# CAN.net
KiCad netlist of a schematic drawn in Altium Designer
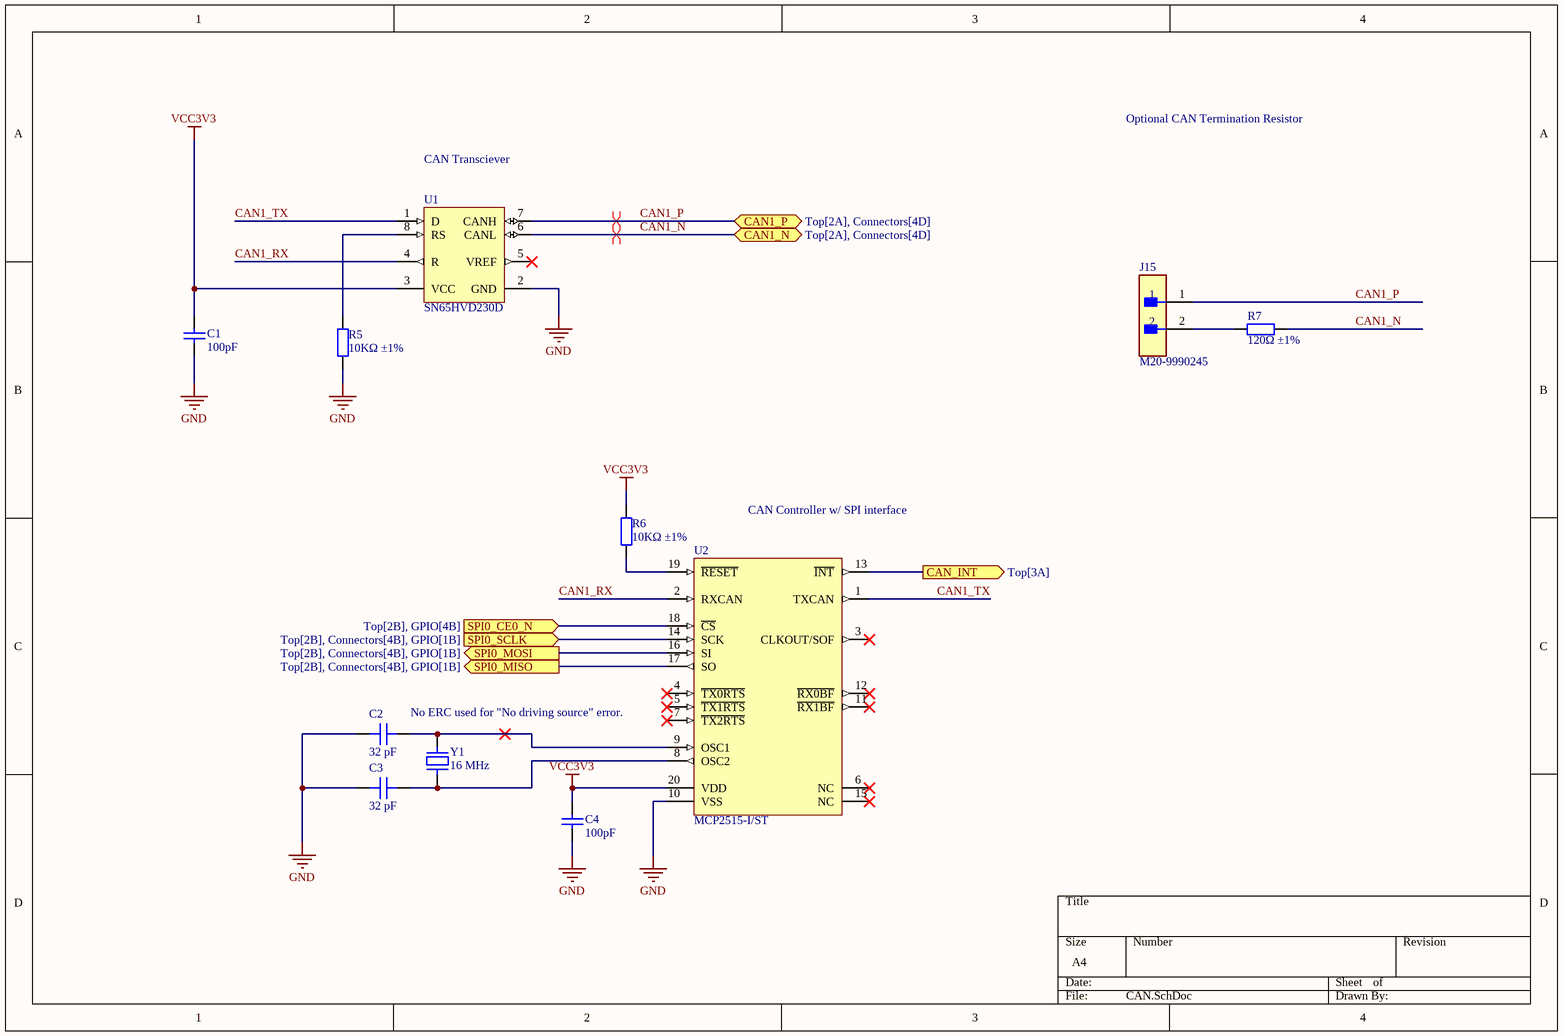
[diagram p0: CAN.SchDoc]

(export (version "E")
  (design (tool "Eeschema 10.0.6"))
  (components
    (comp (ref "C1")
      (value "100pF")
      (footprint "0402_C")
      (description "Chip capacitors")
      (fields
        (field (name "MANUFACTURER") "Guangdong Fenghua Advanced Tech")
        (field (name "PARTNUMBER") "0402CG101J500NT")
      )
      (libsource (lib "Cap") (part "0402 100pF (101) 5% 50V"))
    )
    (comp (ref "C2")
      (value "32 pF")
      (footprint "CAP 0603_1608")
      (description "CAP CER 32PF 100V C0G/NP0 0603")
      (fields (field (name "PART NUMBER") "06031A320FAT2A") (field (name "MANUFACTURER") "KYOCERA AVX"))
      (libsource (lib "Celestial Altium Library - altium_library") (part "Capacitor"))
    )
    (comp (ref "C3")
      (value "32 pF")
      (footprint "CAP 0603_1608")
      (description "CAP CER 32PF 100V C0G/NP0 0603")
      (fields (field (name "PART NUMBER") "06031A320FAT2A") (field (name "MANUFACTURER") "KYOCERA AVX"))
      (libsource (lib "Celestial Altium Library - altium_library") (part "Capacitor"))
    )
    (comp (ref "C4")
      (value "100pF")
      (footprint "0402_C")
      (description "Chip capacitors")
      (fields
        (field (name "MANUFACTURER") "Guangdong Fenghua Advanced Tech")
        (field (name "PARTNUMBER") "0402CG101J500NT")
      )
      (libsource (lib "Cap") (part "0402 100pF (101) 5% 50V"))
    )
    (comp (ref "J15")
      (value "M20-9990245")
      (footprint "FP-M20-9990245-MFG")
      (description "CONN HEADER VERT 2POS 2.54MM")
      (fields (field (name "VOLTAGE") "50V"))
      (libsource (lib "Altium Content Vault") (part "3bc925449376181038e59eaffc5286c"))
    )
    (comp (ref "R5")
      (value "10KΩ ±1%")
      (footprint "0402_R")
      (description "Chip resistor")
      (fields (field (name "MANUFACTURER") "Uniroyal Elec") (field (name "PARTNUMBER") "0402WGF1002TCE"))
      (libsource (lib "RES") (part "0402 10K (1002) 1%"))
    )
    (comp (ref "R6")
      (value "10KΩ ±1%")
      (footprint "0402_R")
      (description "Chip resistor")
      (fields (field (name "MANUFACTURER") "Uniroyal Elec") (field (name "PARTNUMBER") "0402WGF1002TCE"))
      (libsource (lib "RES") (part "0402 10K (1002) 1%"))
    )
    (comp (ref "R7")
      (value "120Ω ±1%")
      (footprint "0603_R")
      (description "Chip resistor")
      (fields (field (name "MANUFACTURER") "Uniroyal Elec") (field (name "PARTNUMBER") "0603WAF1200T5E"))
      (libsource (lib "RES") (part "0603 120R (1200) 1%"))
    )
    (comp (ref "U1")
      (value "SN65HVD230D")
      (footprint "D0008A_M")
      (description "CAN Bus Transceiver, 3.3 V, -40 to 85 degC, 8-Pin SOIC (D), Green (RoHS & no Sb/Br), Tube")
      (fields (field (name "GENERIC PART NUMBER") "SN65HVD230"))
      (libsource (lib "Altium Content Vault") (part "TI-SN65HVD230D-SOIC_D-8"))
    )
    (comp (ref "U2")
      (value "MCP2515-I/ST")
      (footprint "TSSOP-ST20_N")
      (description "Stand-Alone CAN Controller With SPI Interface, 20-Pin TSSOP, Industrial Temperature")
      (libsource (lib "Altium Content Vault") (part "COM-CAN-MCP2515-20"))
    )
    (comp (ref "Y1")
      (value "16 MHz")
      (footprint "ABRACON ABLS")
      (description "CRYSTAL 16.0000MHZ 18PF SMD")
      (fields
        (field (name "PART NUMBER") "ABLS-16.000MHZ-D-3-Y-T")
        (field (name "MANUFACTURER") "Abracon LLC")
      )
      (libsource (lib "Celestial Altium Library - altium_library") (part "Abracon Crystal ABLS"))
    )
  )
  (nets
    (net (code "1") (name "/CAN1_N") (class "Default")
      (node (ref "R7") (pin "1") (pinfunction "1_1") (pintype "passive"))
      (node (ref "U1") (pin "6") (pinfunction "CANL_6") (pintype "bidirectional"))
    )
    (net (code "2") (name "/CAN1_P") (class "Default")
      (node (ref "J15") (pin "1") (pinfunction "1_1") (pintype "passive"))
      (node (ref "U1") (pin "7") (pinfunction "CANH_7") (pintype "bidirectional"))
    )
    (net (code "3") (name "/CAN1_RX") (class "Default")
      (node (ref "U1") (pin "4") (pinfunction "R_4") (pintype "output"))
      (node (ref "U2") (pin "2") (pinfunction "RXCAN_2") (pintype "input"))
    )
    (net (code "4") (name "/CAN1_TX") (class "Default")
      (node (ref "U1") (pin "1") (pinfunction "D_1") (pintype "input"))
      (node (ref "U2") (pin "1") (pinfunction "TXCAN_1") (pintype "output"))
    )
    (net (code "5") (name "/CAN_INT") (class "Default")
      (node (ref "U2") (pin "13") (pinfunction "~{INT}_13") (pintype "output"))
    )
    (net (code "6") (name "/SPI0_CE0_N") (class "Default")
      (node (ref "U2") (pin "18") (pinfunction "~{CS}_18") (pintype "input"))
    )
    (net (code "7") (name "/SPI0_MISO") (class "Default")
      (node (ref "U2") (pin "17") (pinfunction "SO_17") (pintype "output"))
    )
    (net (code "8") (name "/SPI0_MOSI") (class "Default")
      (node (ref "U2") (pin "16") (pinfunction "SI_16") (pintype "input"))
    )
    (net (code "9") (name "/SPI0_SCLK") (class "Default")
      (node (ref "U2") (pin "14") (pinfunction "SCK_14") (pintype "input"))
    )
    (net (code "10") (name "GND") (class "Default")
      (node (ref "C1") (pin "1") (pinfunction "1_1") (pintype "passive"))
      (node (ref "C2") (pin "1") (pinfunction "1_1") (pintype "passive"))
      (node (ref "C3") (pin "1") (pinfunction "1_1") (pintype "passive"))
      (node (ref "C4") (pin "1") (pinfunction "1_1") (pintype "passive"))
      (node (ref "R5") (pin "1") (pinfunction "1_1") (pintype "passive"))
      (node (ref "U1") (pin "2") (pinfunction "GND_2") (pintype "power_in"))
      (node (ref "U2") (pin "10") (pinfunction "VSS_10") (pintype "power_in"))
    )
    (net (code "11") (name "Net-(J15-Pad2)") (class "Default")
      (node (ref "J15") (pin "2") (pinfunction "2_2") (pintype "passive"))
      (node (ref "R7") (pin "2") (pinfunction "2_2") (pintype "passive"))
    )
    (net (code "12") (name "Net-(U1-RS)") (class "Default")
      (node (ref "R5") (pin "2") (pinfunction "2_2") (pintype "passive"))
      (node (ref "U1") (pin "8") (pinfunction "RS_8") (pintype "input"))
    )
    (net (code "13") (name "Net-(U2-OSC1)") (class "Default")
      (node (ref "C2") (pin "2") (pinfunction "2_2") (pintype "passive"))
      (node (ref "U2") (pin "9") (pinfunction "OSC1_9") (pintype "input"))
      (node (ref "Y1") (pin "2") (pinfunction "2_2") (pintype "passive"))
    )
    (net (code "14") (name "Net-(U2-OSC2)") (class "Default")
      (node (ref "C3") (pin "2") (pinfunction "2_2") (pintype "passive"))
      (node (ref "U2") (pin "8") (pinfunction "OSC2_8") (pintype "output"))
      (node (ref "Y1") (pin "1") (pinfunction "1_1") (pintype "passive"))
    )
    (net (code "15") (name "Net-(U2-~{RESET})") (class "Default")
      (node (ref "R6") (pin "1") (pinfunction "1_1") (pintype "passive"))
      (node (ref "U2") (pin "19") (pinfunction "~{RESET}_19") (pintype "input"))
    )
    (net (code "16") (name "VCC3V3") (class "Default")
      (node (ref "C1") (pin "2") (pinfunction "2_2") (pintype "passive"))
      (node (ref "C4") (pin "2") (pinfunction "2_2") (pintype "passive"))
      (node (ref "R6") (pin "2") (pinfunction "2_2") (pintype "passive"))
      (node (ref "U1") (pin "3") (pinfunction "VCC_3") (pintype "power_in"))
      (node (ref "U2") (pin "20") (pinfunction "VDD_20") (pintype "power_in"))
    )
    (net (code "17") (name "unconnected-(U1-VREF-Pad5)") (class "Default")
      (node (ref "U1") (pin "5") (pinfunction "VREF_5") (pintype "output+no_connect"))
    )
    (net (code "18") (name "unconnected-(U2-CLKOUT{slash}SOF-Pad3)") (class "Default")
      (node (ref "U2") (pin "3") (pinfunction "CLKOUT/SOF_3") (pintype "output+no_connect"))
    )
    (net (code "19") (name "unconnected-(U2-NC-Pad6)") (class "Default")
      (node (ref "U2") (pin "6") (pinfunction "NC_6") (pintype "passive+no_connect"))
    )
    (net (code "20") (name "unconnected-(U2-NC-Pad15)") (class "Default")
      (node (ref "U2") (pin "15") (pinfunction "NC_15") (pintype "passive+no_connect"))
    )
    (net (code "21") (name "unconnected-(U2-~{RX0BF}-Pad12)") (class "Default")
      (node (ref "U2") (pin "12") (pinfunction "~{RX0BF}_12") (pintype "output+no_connect"))
    )
    (net (code "22") (name "unconnected-(U2-~{RX1BF}-Pad11)") (class "Default")
      (node (ref "U2") (pin "11") (pinfunction "~{RX1BF}_11") (pintype "output+no_connect"))
    )
    (net (code "23") (name "unconnected-(U2-~{TX0RTS}-Pad4)") (class "Default")
      (node (ref "U2") (pin "4") (pinfunction "~{TX0RTS}_4") (pintype "input+no_connect"))
    )
    (net (code "24") (name "unconnected-(U2-~{TX1RTS}-Pad5)") (class "Default")
      (node (ref "U2") (pin "5") (pinfunction "~{TX1RTS}_5") (pintype "input+no_connect"))
    )
    (net (code "25") (name "unconnected-(U2-~{TX2RTS}-Pad7)") (class "Default")
      (node (ref "U2") (pin "7") (pinfunction "~{TX2RTS}_7") (pintype "input+no_connect"))
    )
  )
)
